# pyESP32mini.net
KiCad netlist of a schematic drawn in Altium Designer
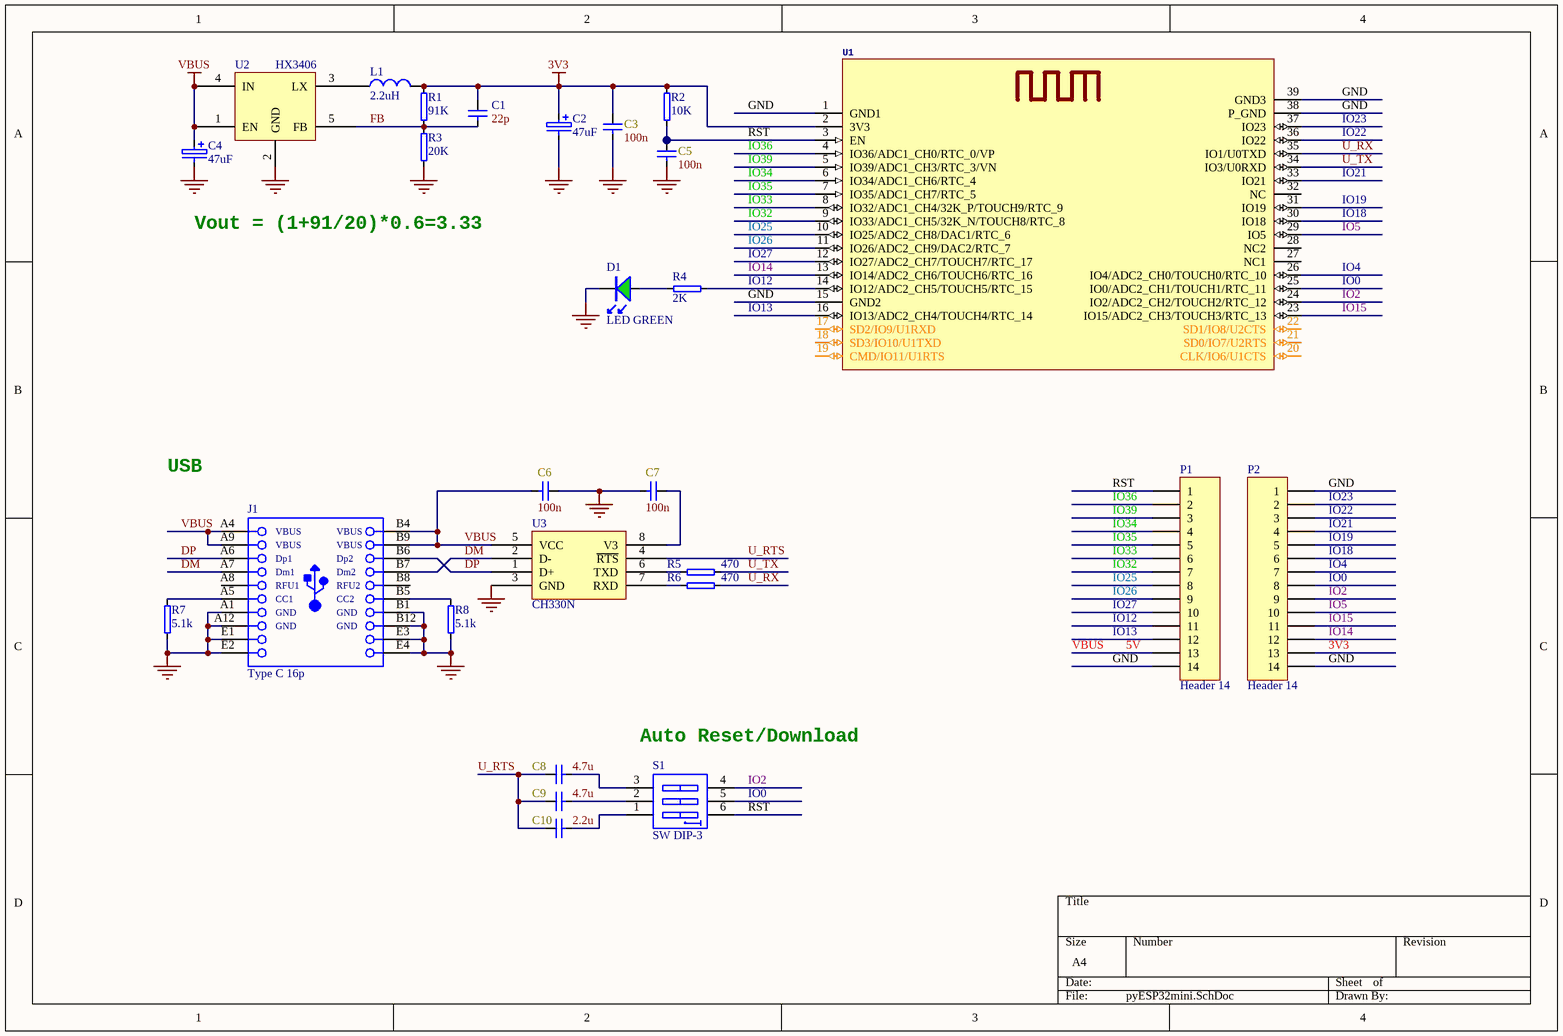
[diagram p0: pyESP32mini.SchDoc]

(export (version "E")
  (design (tool "Eeschema 10.0.6"))
  (components
    (comp (ref "C1") (value "22p") (footprint "C0402") (libsource (lib "s_device") (part "Cap")))
    (comp (ref "C2") (value "47uF") (footprint "3216") (libsource (lib "s_device") (part "E")))
    (comp (ref "C3") (value "100n") (footprint "C0402") (libsource (lib "s_device") (part "Cap")))
    (comp (ref "C4") (value "47uF") (footprint "3216") (libsource (lib "s_device") (part "E")))
    (comp (ref "C5") (value "100n") (footprint "C0402") (libsource (lib "s_device") (part "Cap")))
    (comp (ref "C6") (value "100n") (footprint "C0402") (libsource (lib "s_device") (part "Cap")))
    (comp (ref "C7") (value "100n") (footprint "C0402") (libsource (lib "s_device") (part "Cap")))
    (comp (ref "C8") (value "4.7u") (footprint "C0402") (libsource (lib "s_device") (part "Cap")))
    (comp (ref "C9") (value "4.7u") (footprint "C0402") (libsource (lib "s_device") (part "Cap")))
    (comp (ref "C10") (value "2.2u") (footprint "C0402") (libsource (lib "s_device") (part "Cap")))
    (comp (ref "D1")
      (value "LED GREEN")
      (footprint "LED0402_GREEN")
      (description "Green LED")
      (libsource (lib "s_device") (part "LED-GREEN"))
    )
    (comp (ref "J1")
      (value "Type C 16p")
      (footprint "Type-C 16P")
      (libsource (lib "s_connect") (part "Type C 16p"))
    )
    (comp (ref "L1")
      (value "2.2uH")
      (footprint "IND-252012")
      (fields (field (name "PUBLISHER") "Altium Limited"))
      (libsource (lib "s_device") (part "Inductor"))
    )
    (comp (ref "P1")
      (value "Header 14")
      (footprint "HDR1X14")
      (description "Header, 14-Pin")
      (fields (field (name "PUBLISHER") "Altium Limited"))
      (libsource (lib "Miscellaneous Connectors") (part "Header 14"))
    )
    (comp (ref "P2")
      (value "Header 14")
      (footprint "HDR1X14")
      (description "Header, 14-Pin")
      (fields (field (name "PUBLISHER") "Altium Limited"))
      (libsource (lib "") (part "Header 14_1"))
    )
    (comp (ref "R1") (value "91K") (footprint "SMD0402") (libsource (lib "s_device") (part "Res")))
    (comp (ref "R2") (value "10K") (footprint "SMD0402") (libsource (lib "s_device") (part "Res")))
    (comp (ref "R3") (value "20K") (footprint "SMD0402") (libsource (lib "s_device") (part "Res")))
    (comp (ref "R4") (value "2K") (footprint "SMD0402") (libsource (lib "s_device") (part "Res")))
    (comp (ref "R5") (value "470") (footprint "SMD0402") (libsource (lib "s_device") (part "Res")))
    (comp (ref "R6") (value "470") (footprint "SMD0402") (libsource (lib "s_device") (part "Res")))
    (comp (ref "R7") (value "5.1k") (footprint "SMD0402") (libsource (lib "s_device") (part "Res")))
    (comp (ref "R8") (value "5.1k") (footprint "SMD0402") (libsource (lib "s_device") (part "Res")))
    (comp (ref "S1")
      (value "SW DIP-3")
      (footprint "SW-SMD3")
      (description "DIP Switch, 3 Position, SPST")
      (fields (field (name "PUBLISHER") "Altium Limited"))
      (libsource (lib "s_device") (part "SW DIP-3"))
    )
    (comp (ref "U1")
      (value "ESP32-WROVER")
      (footprint "ESP32-WROVER")
      (libsource (lib "s_misc") (part "ESP32-WROVER"))
    )
    (comp (ref "U2") (value "HX3406") (footprint "SOT23-5") (libsource (lib "s_power") (part "SY8089")))
    (comp (ref "U3") (value "CH330N") (footprint "NSO8_M") (libsource (lib "s_interface") (part "CH330N")))
  )
  (nets
    (net (code "1") (name "/DM") (class "Default")
      (node (ref "J1") (pin "A7") (pinfunction "Dm1_A7") (pintype "passive"))
      (node (ref "J1") (pin "B7") (pinfunction "Dm2_B7") (pintype "passive"))
      (node (ref "U3") (pin "2") (pinfunction "D-_2") (pintype "passive"))
    )
    (net (code "2") (name "/DP") (class "Default")
      (node (ref "J1") (pin "A6") (pinfunction "Dp1_A6") (pintype "passive"))
      (node (ref "J1") (pin "B6") (pinfunction "Dp2_B6") (pintype "passive"))
      (node (ref "U3") (pin "1") (pinfunction "D+_1") (pintype "passive"))
    )
    (net (code "3") (name "/FB") (class "Default")
      (node (ref "C1") (pin "1") (pintype "passive"))
      (node (ref "R1") (pin "1") (pintype "passive"))
      (node (ref "R3") (pin "2") (pintype "passive"))
      (node (ref "U2") (pin "5") (pinfunction "FB_5") (pintype "passive"))
    )
    (net (code "4") (name "/IO0") (class "Default")
      (node (ref "P2") (pin "8") (pinfunction "8_8") (pintype "passive"))
      (node (ref "S1") (pin "5") (pinfunction "B2_5") (pintype "passive"))
      (node (ref "U1") (pin "25") (pinfunction "IO0/ADC2_CH1/TOUCH1/RTC_11_25") (pintype "bidirectional"))
    )
    (net (code "5") (name "/IO2") (class "Default")
      (node (ref "P2") (pin "9") (pinfunction "9_9") (pintype "passive"))
      (node (ref "S1") (pin "4") (pinfunction "B3_4") (pintype "passive"))
      (node (ref "U1") (pin "24") (pinfunction "IO2/ADC2_CH2/TOUCH2/RTC_12_24") (pintype "bidirectional"))
    )
    (net (code "6") (name "/IO4") (class "Default")
      (node (ref "P2") (pin "7") (pinfunction "7_7") (pintype "passive"))
      (node (ref "U1") (pin "26") (pinfunction "IO4/ADC2_CH0/TOUCH0/RTC_10_26") (pintype "bidirectional"))
    )
    (net (code "7") (name "/IO5") (class "Default")
      (node (ref "P2") (pin "10") (pinfunction "10_10") (pintype "passive"))
      (node (ref "U1") (pin "29") (pinfunction "IO5_29") (pintype "bidirectional"))
    )
    (net (code "8") (name "/IO12") (class "Default")
      (node (ref "P1") (pin "11") (pinfunction "11_11") (pintype "passive"))
      (node (ref "R4") (pin "2") (pintype "passive"))
      (node (ref "U1") (pin "14") (pinfunction "IO12/ADC2_CH5/TOUCH5/RTC_15_14") (pintype "bidirectional"))
    )
    (net (code "9") (name "/IO13") (class "Default")
      (node (ref "P1") (pin "12") (pinfunction "12_12") (pintype "passive"))
      (node (ref "U1") (pin "16") (pinfunction "IO13/ADC2_CH4/TOUCH4/RTC_14_16") (pintype "bidirectional"))
    )
    (net (code "10") (name "/IO14") (class "Default")
      (node (ref "P2") (pin "12") (pinfunction "12_12") (pintype "passive"))
      (node (ref "U1") (pin "13") (pinfunction "IO14/ADC2_CH6/TOUCH6/RTC_16_13") (pintype "bidirectional"))
    )
    (net (code "11") (name "/IO15") (class "Default")
      (node (ref "P2") (pin "11") (pinfunction "11_11") (pintype "passive"))
      (node (ref "U1") (pin "23") (pinfunction "IO15/ADC2_CH3/TOUCH3/RTC_13_23") (pintype "bidirectional"))
    )
    (net (code "12") (name "/IO18") (class "Default")
      (node (ref "P2") (pin "6") (pinfunction "6_6") (pintype "passive"))
      (node (ref "U1") (pin "30") (pinfunction "IO18_30") (pintype "bidirectional"))
    )
    (net (code "13") (name "/IO19") (class "Default")
      (node (ref "P2") (pin "5") (pinfunction "5_5") (pintype "passive"))
      (node (ref "U1") (pin "31") (pinfunction "IO19_31") (pintype "bidirectional"))
    )
    (net (code "14") (name "/IO21") (class "Default")
      (node (ref "P2") (pin "4") (pinfunction "4_4") (pintype "passive"))
      (node (ref "U1") (pin "33") (pinfunction "IO21_33") (pintype "bidirectional"))
    )
    (net (code "15") (name "/IO22") (class "Default")
      (node (ref "P2") (pin "3") (pinfunction "3_3") (pintype "passive"))
      (node (ref "U1") (pin "36") (pinfunction "IO22_36") (pintype "bidirectional"))
    )
    (net (code "16") (name "/IO23") (class "Default")
      (node (ref "P2") (pin "2") (pinfunction "2_2") (pintype "passive"))
      (node (ref "U1") (pin "37") (pinfunction "IO23_37") (pintype "bidirectional"))
    )
    (net (code "17") (name "/IO25") (class "Default")
      (node (ref "P1") (pin "8") (pinfunction "8_8") (pintype "passive"))
      (node (ref "U1") (pin "10") (pinfunction "IO25/ADC2_CH8/DAC1/RTC_6_10") (pintype "bidirectional"))
    )
    (net (code "18") (name "/IO26") (class "Default")
      (node (ref "P1") (pin "9") (pinfunction "9_9") (pintype "passive"))
      (node (ref "U1") (pin "11") (pinfunction "IO26/ADC2_CH9/DAC2/RTC_7_11") (pintype "bidirectional"))
    )
    (net (code "19") (name "/IO27") (class "Default")
      (node (ref "P1") (pin "10") (pinfunction "10_10") (pintype "passive"))
      (node (ref "U1") (pin "12") (pinfunction "IO27/ADC2_CH7/TOUCH7/RTC_17_12") (pintype "bidirectional"))
    )
    (net (code "20") (name "/IO32") (class "Default")
      (node (ref "P1") (pin "7") (pinfunction "7_7") (pintype "passive"))
      (node (ref "U1") (pin "9") (pinfunction "IO33/ADC1_CH5/32K_N/TOUCH8/RTC_8_9") (pintype "bidirectional"))
    )
    (net (code "21") (name "/IO33") (class "Default")
      (node (ref "P1") (pin "6") (pinfunction "6_6") (pintype "passive"))
      (node (ref "U1") (pin "8") (pinfunction "IO32/ADC1_CH4/32K_P/TOUCH9/RTC_9_8") (pintype "bidirectional"))
    )
    (net (code "22") (name "/IO34") (class "Default")
      (node (ref "P1") (pin "4") (pinfunction "4_4") (pintype "passive"))
      (node (ref "U1") (pin "6") (pinfunction "IO34/ADC1_CH6/RTC_4_6") (pintype "input"))
    )
    (net (code "23") (name "/IO35") (class "Default")
      (node (ref "P1") (pin "5") (pinfunction "5_5") (pintype "passive"))
      (node (ref "U1") (pin "7") (pinfunction "IO35/ADC1_CH7/RTC_5_7") (pintype "input"))
    )
    (net (code "24") (name "/IO36") (class "Default")
      (node (ref "P1") (pin "2") (pinfunction "2_2") (pintype "passive"))
      (node (ref "U1") (pin "4") (pinfunction "IO36/ADC1_CH0/RTC_0/VP_4") (pintype "input"))
    )
    (net (code "25") (name "/IO39") (class "Default")
      (node (ref "P1") (pin "3") (pinfunction "3_3") (pintype "passive"))
      (node (ref "U1") (pin "5") (pinfunction "IO39/ADC1_CH3/RTC_3/VN_5") (pintype "input"))
    )
    (net (code "26") (name "/RST") (class "Default")
      (node (ref "C5") (pin "2") (pintype "passive"))
      (node (ref "P1") (pin "1") (pinfunction "1_1") (pintype "passive"))
      (node (ref "R2") (pin "1") (pintype "passive"))
      (node (ref "S1") (pin "6") (pinfunction "B1_6") (pintype "passive"))
      (node (ref "U1") (pin "3") (pinfunction "EN_3") (pintype "input"))
    )
    (net (code "27") (name "/U_RTS") (class "Default")
      (node (ref "C10") (pin "2") (pintype "passive"))
      (node (ref "C8") (pin "2") (pintype "passive"))
      (node (ref "C9") (pin "2") (pintype "passive"))
      (node (ref "U3") (pin "4") (pinfunction "~{RTS}_4") (pintype "passive"))
    )
    (net (code "28") (name "/U_RX") (class "Default")
      (node (ref "R6") (pin "2") (pintype "passive"))
      (node (ref "U1") (pin "35") (pinfunction "IO1/U0TXD_35") (pintype "bidirectional"))
    )
    (net (code "29") (name "/U_TX") (class "Default")
      (node (ref "R5") (pin "2") (pintype "passive"))
      (node (ref "U1") (pin "34") (pinfunction "IO3/U0RXD_34") (pintype "bidirectional"))
    )
    (net (code "30") (name "3V3") (class "Default")
      (node (ref "C1") (pin "2") (pintype "passive"))
      (node (ref "C2") (pin "1") (pintype "passive"))
      (node (ref "C3") (pin "2") (pintype "passive"))
      (node (ref "L1") (pin "2") (pinfunction "2_2") (pintype "passive"))
      (node (ref "P2") (pin "13") (pinfunction "13_13") (pintype "passive"))
      (node (ref "R1") (pin "2") (pintype "passive"))
      (node (ref "R2") (pin "2") (pintype "passive"))
      (node (ref "U1") (pin "2") (pinfunction "3V3_2") (pintype "power_in"))
    )
    (net (code "31") (name "GND") (class "Default")
      (node (ref "C2") (pin "2") (pintype "passive"))
      (node (ref "C3") (pin "1") (pintype "passive"))
      (node (ref "C4") (pin "2") (pintype "passive"))
      (node (ref "C5") (pin "1") (pintype "passive"))
      (node (ref "C6") (pin "2") (pintype "passive"))
      (node (ref "C7") (pin "1") (pintype "passive"))
      (node (ref "D1") (pin "2") (pintype "passive"))
      (node (ref "J1") (pin "A1") (pinfunction "GND_A1") (pintype "passive"))
      (node (ref "J1") (pin "A12") (pinfunction "GND_A12") (pintype "passive"))
      (node (ref "J1") (pin "B1") (pinfunction "GND_B1") (pintype "passive"))
      (node (ref "J1") (pin "B12") (pinfunction "GND_B12") (pintype "passive"))
      (node (ref "J1") (pin "E1") (pinfunction "E1_E1") (pintype "passive"))
      (node (ref "J1") (pin "E2") (pintype "passive"))
      (node (ref "J1") (pin "E3") (pinfunction "E3_E3") (pintype "passive"))
      (node (ref "J1") (pin "E4") (pintype "passive"))
      (node (ref "P1") (pin "14") (pinfunction "14_14") (pintype "passive"))
      (node (ref "P2") (pin "1") (pinfunction "1_1") (pintype "passive"))
      (node (ref "P2") (pin "14") (pinfunction "14_14") (pintype "passive"))
      (node (ref "R3") (pin "1") (pintype "passive"))
      (node (ref "R7") (pin "2") (pintype "passive"))
      (node (ref "R8") (pin "2") (pintype "passive"))
      (node (ref "U1") (pin "1") (pinfunction "GND1_1") (pintype "power_in"))
      (node (ref "U1") (pin "15") (pinfunction "GND2_15") (pintype "power_in"))
      (node (ref "U1") (pin "38") (pinfunction "P_GND_38") (pintype "power_in"))
      (node (ref "U1") (pin "39") (pinfunction "GND3_39") (pintype "power_in"))
      (node (ref "U2") (pin "2") (pinfunction "GND_2") (pintype "passive"))
      (node (ref "U3") (pin "3") (pinfunction "GND_3") (pintype "passive"))
    )
    (net (code "32") (name "Net-(D1-Pad1)") (class "Default")
      (node (ref "D1") (pin "1") (pintype "passive"))
      (node (ref "R4") (pin "1") (pintype "passive"))
    )
    (net (code "33") (name "Net-(J1-CC1)") (class "Default")
      (node (ref "J1") (pin "A5") (pinfunction "CC1_A5") (pintype "passive"))
      (node (ref "R7") (pin "1") (pintype "passive"))
    )
    (net (code "34") (name "Net-(J1-CC2)") (class "Default")
      (node (ref "J1") (pin "B5") (pinfunction "CC2_B5") (pintype "passive"))
      (node (ref "R8") (pin "1") (pintype "passive"))
    )
    (net (code "35") (name "Net-(S1-A1)") (class "Default")
      (node (ref "C10") (pin "1") (pintype "passive"))
      (node (ref "S1") (pin "1") (pinfunction "A1_1") (pintype "passive"))
    )
    (net (code "36") (name "Net-(S1-A2)") (class "Default")
      (node (ref "C9") (pin "1") (pintype "passive"))
      (node (ref "S1") (pin "2") (pinfunction "A2_2") (pintype "passive"))
    )
    (net (code "37") (name "Net-(S1-A3)") (class "Default")
      (node (ref "C8") (pin "1") (pintype "passive"))
      (node (ref "S1") (pin "3") (pinfunction "A3_3") (pintype "passive"))
    )
    (net (code "38") (name "Net-(U2-LX)") (class "Default")
      (node (ref "L1") (pin "1") (pinfunction "1_1") (pintype "passive"))
      (node (ref "U2") (pin "3") (pinfunction "LX_3") (pintype "passive"))
    )
    (net (code "39") (name "Net-(U3-RXD)") (class "Default")
      (node (ref "R6") (pin "1") (pintype "passive"))
      (node (ref "U3") (pin "7") (pinfunction "RXD_7") (pintype "passive"))
    )
    (net (code "40") (name "Net-(U3-TXD)") (class "Default")
      (node (ref "R5") (pin "1") (pintype "passive"))
      (node (ref "U3") (pin "6") (pinfunction "TXD_6") (pintype "passive"))
    )
    (net (code "41") (name "Net-(U3-V3)") (class "Default")
      (node (ref "C7") (pin "2") (pintype "passive"))
      (node (ref "U3") (pin "8") (pinfunction "V3_8") (pintype "passive"))
    )
    (net (code "42") (name "VBUS") (class "Default")
      (node (ref "C4") (pin "1") (pintype "passive"))
      (node (ref "C6") (pin "1") (pintype "passive"))
      (node (ref "J1") (pin "A4") (pinfunction "VBUS_A4") (pintype "passive"))
      (node (ref "J1") (pin "A9") (pinfunction "VBUS_A9") (pintype "passive"))
      (node (ref "J1") (pin "B4") (pinfunction "VBUS_B4") (pintype "passive"))
      (node (ref "J1") (pin "B9") (pinfunction "VBUS_B9") (pintype "passive"))
      (node (ref "P1") (pin "13") (pinfunction "13_13") (pintype "passive"))
      (node (ref "U2") (pin "1") (pinfunction "EN_1") (pintype "passive"))
      (node (ref "U2") (pin "4") (pinfunction "IN_4") (pintype "passive"))
      (node (ref "U3") (pin "5") (pinfunction "VCC_5") (pintype "passive"))
    )
    (net (code "43") (name "unconnected-(J1-RFU1-PadA8)") (class "Default")
      (node (ref "J1") (pin "A8") (pinfunction "RFU1_A8") (pintype "passive"))
    )
    (net (code "44") (name "unconnected-(J1-RFU2-PadB8)") (class "Default")
      (node (ref "J1") (pin "B8") (pinfunction "RFU2_B8") (pintype "passive"))
    )
    (net (code "45") (name "unconnected-(U1-CLK{slash}IO6{slash}U1CTS-Pad20)") (class "Default")
      (node (ref "U1") (pin "20") (pinfunction "CLK/IO6/U1CTS_20") (pintype "bidirectional"))
    )
    (net (code "46") (name "unconnected-(U1-CMD{slash}IO11{slash}U1RTS-Pad19)") (class "Default")
      (node (ref "U1") (pin "19") (pinfunction "CMD/IO11/U1RTS_19") (pintype "bidirectional"))
    )
    (net (code "47") (name "unconnected-(U1-NC-Pad32)") (class "Default")
      (node (ref "U1") (pin "32") (pinfunction "NC_32") (pintype "passive"))
    )
    (net (code "48") (name "unconnected-(U1-NC1-Pad27)") (class "Default")
      (node (ref "U1") (pin "27") (pinfunction "NC1_27") (pintype "passive"))
    )
    (net (code "49") (name "unconnected-(U1-NC2-Pad28)") (class "Default")
      (node (ref "U1") (pin "28") (pinfunction "NC2_28") (pintype "passive"))
    )
    (net (code "50") (name "unconnected-(U1-SD0{slash}IO7{slash}U2RTS-Pad21)") (class "Default")
      (node (ref "U1") (pin "21") (pinfunction "SD0/IO7/U2RTS_21") (pintype "bidirectional"))
    )
    (net (code "51") (name "unconnected-(U1-SD1{slash}IO8{slash}U2CTS-Pad22)") (class "Default")
      (node (ref "U1") (pin "22") (pinfunction "SD1/IO8/U2CTS_22") (pintype "bidirectional"))
    )
    (net (code "52") (name "unconnected-(U1-SD2{slash}IO9{slash}U1RXD-Pad17)") (class "Default")
      (node (ref "U1") (pin "17") (pinfunction "SD2/IO9/U1RXD_17") (pintype "bidirectional"))
    )
    (net (code "53") (name "unconnected-(U1-SD3{slash}IO10{slash}U1TXD-Pad18)") (class "Default")
      (node (ref "U1") (pin "18") (pinfunction "SD3/IO10/U1TXD_18") (pintype "bidirectional"))
    )
  )
)
